# M633B.net
KiCad netlist of a schematic drawn in EAGLE
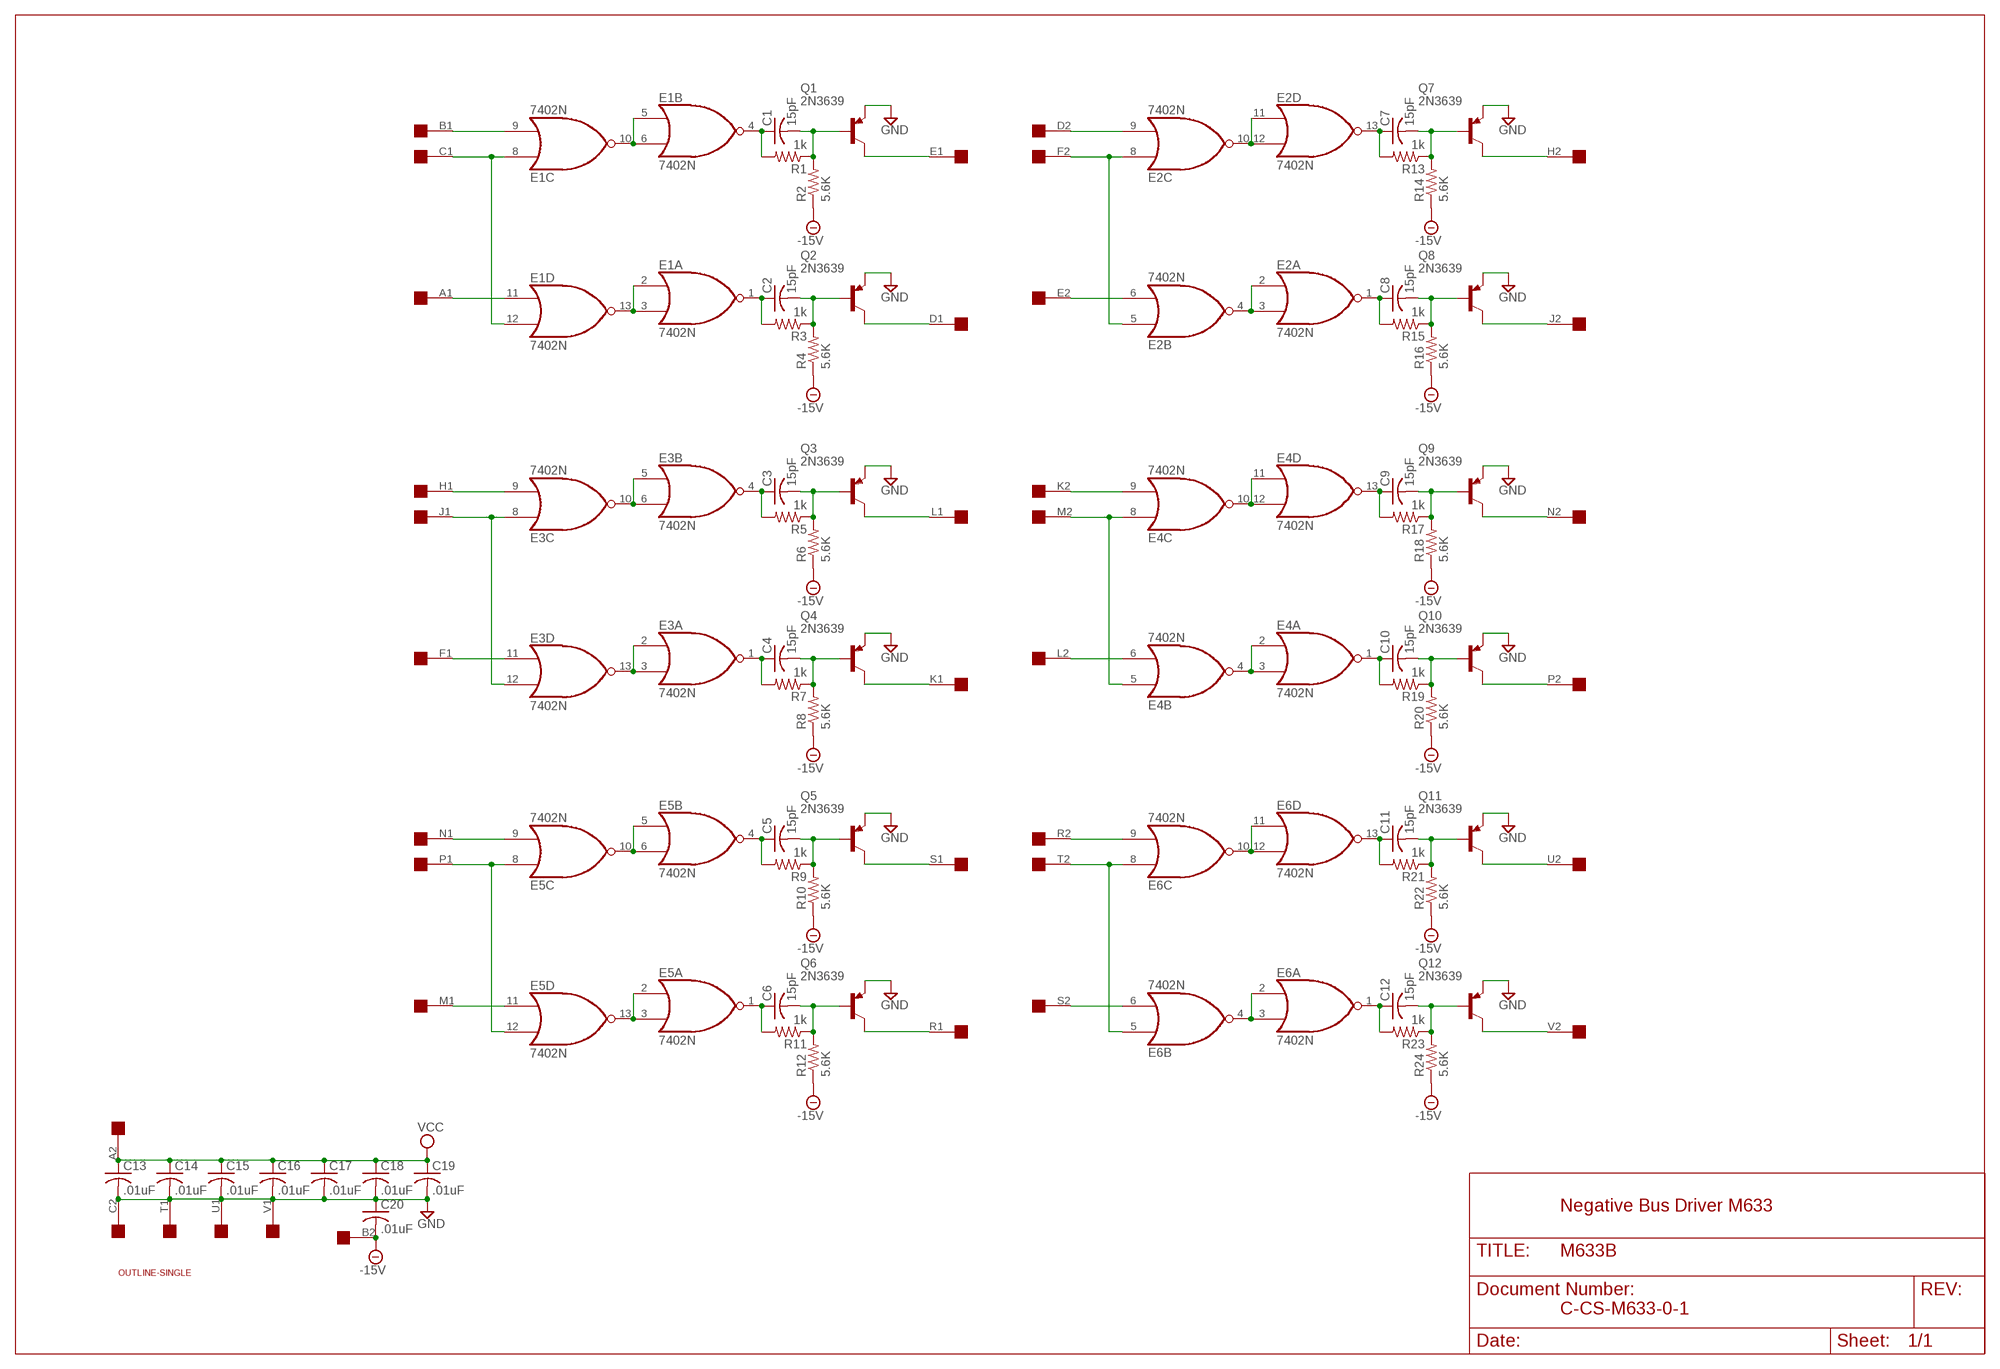
[diagram p0: schematic, sheet 1]

(export (version "E")
  (design (tool "Eeschema 10.0.6"))
  (components
    (comp (ref "C1")
      (value "15pF")
      (footprint "eagle-import:C050-025X075")
      (libsource (lib "eagle-import") (part "C-US050-025X075"))
    )
    (comp (ref "C2")
      (value "15pF")
      (footprint "eagle-import:C050-025X075")
      (libsource (lib "eagle-import") (part "C-US050-025X075"))
    )
    (comp (ref "C3")
      (value "15pF")
      (footprint "eagle-import:C050-025X075")
      (libsource (lib "eagle-import") (part "C-US050-025X075"))
    )
    (comp (ref "C4")
      (value "15pF")
      (footprint "eagle-import:C050-025X075")
      (libsource (lib "eagle-import") (part "C-US050-025X075"))
    )
    (comp (ref "C5")
      (value "15pF")
      (footprint "eagle-import:C050-025X075")
      (libsource (lib "eagle-import") (part "C-US050-025X075"))
    )
    (comp (ref "C6")
      (value "15pF")
      (footprint "eagle-import:C050-025X075")
      (libsource (lib "eagle-import") (part "C-US050-025X075"))
    )
    (comp (ref "C7")
      (value "15pF")
      (footprint "eagle-import:C050-025X075")
      (libsource (lib "eagle-import") (part "C-US050-025X075"))
    )
    (comp (ref "C8")
      (value "15pF")
      (footprint "eagle-import:C050-025X075")
      (libsource (lib "eagle-import") (part "C-US050-025X075"))
    )
    (comp (ref "C9")
      (value "15pF")
      (footprint "eagle-import:C050-025X075")
      (libsource (lib "eagle-import") (part "C-US050-025X075"))
    )
    (comp (ref "C10")
      (value "15pF")
      (footprint "eagle-import:C050-025X075")
      (libsource (lib "eagle-import") (part "C-US050-025X075"))
    )
    (comp (ref "C11")
      (value "15pF")
      (footprint "eagle-import:C050-025X075")
      (libsource (lib "eagle-import") (part "C-US050-025X075"))
    )
    (comp (ref "C12")
      (value "15pF")
      (footprint "eagle-import:C050-025X075")
      (libsource (lib "eagle-import") (part "C-US050-025X075"))
    )
    (comp (ref "C13")
      (value ".01uF")
      (footprint "eagle-import:C050-025X075")
      (libsource (lib "eagle-import") (part "C-US050-025X075"))
    )
    (comp (ref "C14")
      (value ".01uF")
      (footprint "eagle-import:C050-025X075")
      (libsource (lib "eagle-import") (part "C-US050-025X075"))
    )
    (comp (ref "C15")
      (value ".01uF")
      (footprint "eagle-import:C050-025X075")
      (libsource (lib "eagle-import") (part "C-US050-025X075"))
    )
    (comp (ref "C16")
      (value ".01uF")
      (footprint "eagle-import:C050-025X075")
      (libsource (lib "eagle-import") (part "C-US050-025X075"))
    )
    (comp (ref "C17")
      (value ".01uF")
      (footprint "eagle-import:C050-025X075")
      (libsource (lib "eagle-import") (part "C-US050-025X075"))
    )
    (comp (ref "C18")
      (value ".01uF")
      (footprint "eagle-import:C050-025X075")
      (libsource (lib "eagle-import") (part "C-US050-025X075"))
    )
    (comp (ref "C19")
      (value ".01uF")
      (footprint "eagle-import:C050-025X075")
      (libsource (lib "eagle-import") (part "C-US050-025X075"))
    )
    (comp (ref "C20")
      (value ".01uF")
      (footprint "eagle-import:C050-025X075")
      (libsource (lib "eagle-import") (part "C-US050-025X075"))
    )
    (comp (ref "E1")
      (value "7402N")
      (footprint "eagle-import:DIL14")
      (libsource (lib "eagle-import") (part "7402N"))
    )
    (comp (ref "E2")
      (value "7402N")
      (footprint "eagle-import:DIL14")
      (libsource (lib "eagle-import") (part "7402N"))
    )
    (comp (ref "E3")
      (value "7402N")
      (footprint "eagle-import:DIL14")
      (libsource (lib "eagle-import") (part "7402N"))
    )
    (comp (ref "E4")
      (value "7402N")
      (footprint "eagle-import:DIL14")
      (libsource (lib "eagle-import") (part "7402N"))
    )
    (comp (ref "E5")
      (value "7402N")
      (footprint "eagle-import:DIL14")
      (libsource (lib "eagle-import") (part "7402N"))
    )
    (comp (ref "E6")
      (value "7402N")
      (footprint "eagle-import:DIL14")
      (libsource (lib "eagle-import") (part "7402N"))
    )
    (comp (ref "Q1")
      (value "2N3639")
      (footprint "eagle-import:TO39")
      (libsource (lib "eagle-import") (part "2N5415"))
    )
    (comp (ref "Q2")
      (value "2N3639")
      (footprint "eagle-import:TO39")
      (libsource (lib "eagle-import") (part "2N5415"))
    )
    (comp (ref "Q3")
      (value "2N3639")
      (footprint "eagle-import:TO39")
      (libsource (lib "eagle-import") (part "2N5415"))
    )
    (comp (ref "Q4")
      (value "2N3639")
      (footprint "eagle-import:TO39")
      (libsource (lib "eagle-import") (part "2N5415"))
    )
    (comp (ref "Q5")
      (value "2N3639")
      (footprint "eagle-import:TO39")
      (libsource (lib "eagle-import") (part "2N5415"))
    )
    (comp (ref "Q6")
      (value "2N3639")
      (footprint "eagle-import:TO39")
      (libsource (lib "eagle-import") (part "2N5415"))
    )
    (comp (ref "Q7")
      (value "2N3639")
      (footprint "eagle-import:TO39")
      (libsource (lib "eagle-import") (part "2N5415"))
    )
    (comp (ref "Q8")
      (value "2N3639")
      (footprint "eagle-import:TO39")
      (libsource (lib "eagle-import") (part "2N5415"))
    )
    (comp (ref "Q9")
      (value "2N3639")
      (footprint "eagle-import:TO39")
      (libsource (lib "eagle-import") (part "2N5415"))
    )
    (comp (ref "Q10")
      (value "2N3639")
      (footprint "eagle-import:TO39")
      (libsource (lib "eagle-import") (part "2N5415"))
    )
    (comp (ref "Q11")
      (value "2N3639")
      (footprint "eagle-import:TO39")
      (libsource (lib "eagle-import") (part "2N5415"))
    )
    (comp (ref "Q12")
      (value "2N3639")
      (footprint "eagle-import:TO39")
      (libsource (lib "eagle-import") (part "2N5415"))
    )
    (comp (ref "R1")
      (value "1k")
      (footprint "eagle-import:0207_10")
      (libsource (lib "eagle-import") (part "R-US_0207/10"))
    )
    (comp (ref "R2")
      (value "5.6K")
      (footprint "eagle-import:0207_10")
      (libsource (lib "eagle-import") (part "R-US_0207/10"))
    )
    (comp (ref "R3")
      (value "1k")
      (footprint "eagle-import:0207_10")
      (libsource (lib "eagle-import") (part "R-US_0207/10"))
    )
    (comp (ref "R4")
      (value "5.6K")
      (footprint "eagle-import:0207_10")
      (libsource (lib "eagle-import") (part "R-US_0207/10"))
    )
    (comp (ref "R5")
      (value "1k")
      (footprint "eagle-import:0207_10")
      (libsource (lib "eagle-import") (part "R-US_0207/10"))
    )
    (comp (ref "R6")
      (value "5.6K")
      (footprint "eagle-import:0207_10")
      (libsource (lib "eagle-import") (part "R-US_0207/10"))
    )
    (comp (ref "R7")
      (value "1k")
      (footprint "eagle-import:0207_10")
      (libsource (lib "eagle-import") (part "R-US_0207/10"))
    )
    (comp (ref "R8")
      (value "5.6K")
      (footprint "eagle-import:0207_10")
      (libsource (lib "eagle-import") (part "R-US_0207/10"))
    )
    (comp (ref "R9")
      (value "1k")
      (footprint "eagle-import:0207_10")
      (libsource (lib "eagle-import") (part "R-US_0207/10"))
    )
    (comp (ref "R10")
      (value "5.6K")
      (footprint "eagle-import:0207_10")
      (libsource (lib "eagle-import") (part "R-US_0207/10"))
    )
    (comp (ref "R11")
      (value "1k")
      (footprint "eagle-import:0207_10")
      (libsource (lib "eagle-import") (part "R-US_0207/10"))
    )
    (comp (ref "R12")
      (value "5.6K")
      (footprint "eagle-import:0207_10")
      (libsource (lib "eagle-import") (part "R-US_0207/10"))
    )
    (comp (ref "R13")
      (value "1k")
      (footprint "eagle-import:0207_10")
      (libsource (lib "eagle-import") (part "R-US_0207/10"))
    )
    (comp (ref "R14")
      (value "5.6K")
      (footprint "eagle-import:0207_10")
      (libsource (lib "eagle-import") (part "R-US_0207/10"))
    )
    (comp (ref "R15")
      (value "1k")
      (footprint "eagle-import:0207_10")
      (libsource (lib "eagle-import") (part "R-US_0207/10"))
    )
    (comp (ref "R16")
      (value "5.6K")
      (footprint "eagle-import:0207_10")
      (libsource (lib "eagle-import") (part "R-US_0207/10"))
    )
    (comp (ref "R17")
      (value "1k")
      (footprint "eagle-import:0207_10")
      (libsource (lib "eagle-import") (part "R-US_0207/10"))
    )
    (comp (ref "R18")
      (value "5.6K")
      (footprint "eagle-import:0207_10")
      (libsource (lib "eagle-import") (part "R-US_0207/10"))
    )
    (comp (ref "R19")
      (value "1k")
      (footprint "eagle-import:0207_10")
      (libsource (lib "eagle-import") (part "R-US_0207/10"))
    )
    (comp (ref "R20")
      (value "5.6K")
      (footprint "eagle-import:0207_10")
      (libsource (lib "eagle-import") (part "R-US_0207/10"))
    )
    (comp (ref "R21")
      (value "1k")
      (footprint "eagle-import:0207_10")
      (libsource (lib "eagle-import") (part "R-US_0207/10"))
    )
    (comp (ref "R22")
      (value "5.6K")
      (footprint "eagle-import:0207_10")
      (libsource (lib "eagle-import") (part "R-US_0207/10"))
    )
    (comp (ref "R23")
      (value "1k")
      (footprint "eagle-import:0207_10")
      (libsource (lib "eagle-import") (part "R-US_0207/10"))
    )
    (comp (ref "R24")
      (value "5.6K")
      (footprint "eagle-import:0207_10")
      (libsource (lib "eagle-import") (part "R-US_0207/10"))
    )
    (comp (ref "U$1")
      (value "OUTLINE-SINGLE")
      (footprint "eagle-import:SINGLE")
      (libsource (lib "eagle-import") (part "OUTLINE-SINGLE"))
    )
    (comp (ref "U$4")
      (value "SINGLE")
      (footprint "eagle-import:EDGE-CON2")
      (libsource (lib "eagle-import") (part "SINGLE"))
    )
  )
  (nets
    (net (code "1") (name "-15V") (class "Default")
      (node (ref "C20") (pin "2") (pinfunction "2_2") (pintype "passive"))
      (node (ref "R10") (pin "1") (pinfunction "1_1") (pintype "passive"))
      (node (ref "R12") (pin "1") (pinfunction "1_1") (pintype "passive"))
      (node (ref "R14") (pin "1") (pinfunction "1_1") (pintype "passive"))
      (node (ref "R16") (pin "1") (pinfunction "1_1") (pintype "passive"))
      (node (ref "R18") (pin "1") (pinfunction "1_1") (pintype "passive"))
      (node (ref "R2") (pin "1") (pinfunction "1_1") (pintype "passive"))
      (node (ref "R20") (pin "1") (pinfunction "1_1") (pintype "passive"))
      (node (ref "R22") (pin "1") (pinfunction "1_1") (pintype "passive"))
      (node (ref "R24") (pin "1") (pinfunction "1_1") (pintype "passive"))
      (node (ref "R4") (pin "1") (pinfunction "1_1") (pintype "passive"))
      (node (ref "R6") (pin "1") (pinfunction "1_1") (pintype "passive"))
      (node (ref "R8") (pin "1") (pinfunction "1_1") (pintype "passive"))
      (node (ref "U$4") (pin "B2") (pinfunction "1_B2") (pintype "bidirectional"))
    )
    (net (code "2") (name "GND") (class "Default")
      (node (ref "C13") (pin "2") (pinfunction "2_2") (pintype "passive"))
      (node (ref "C14") (pin "2") (pinfunction "2_2") (pintype "passive"))
      (node (ref "C15") (pin "2") (pinfunction "2_2") (pintype "passive"))
      (node (ref "C16") (pin "2") (pinfunction "2_2") (pintype "passive"))
      (node (ref "C17") (pin "2") (pinfunction "2_2") (pintype "passive"))
      (node (ref "C18") (pin "2") (pinfunction "2_2") (pintype "passive"))
      (node (ref "C19") (pin "2") (pinfunction "2_2") (pintype "passive"))
      (node (ref "C20") (pin "1") (pinfunction "1_1") (pintype "passive"))
      (node (ref "Q1") (pin "1") (pinfunction "E_1") (pintype "passive"))
      (node (ref "Q10") (pin "1") (pinfunction "E_1") (pintype "passive"))
      (node (ref "Q11") (pin "1") (pinfunction "E_1") (pintype "passive"))
      (node (ref "Q12") (pin "1") (pinfunction "E_1") (pintype "passive"))
      (node (ref "Q2") (pin "1") (pinfunction "E_1") (pintype "passive"))
      (node (ref "Q3") (pin "1") (pinfunction "E_1") (pintype "passive"))
      (node (ref "Q4") (pin "1") (pinfunction "E_1") (pintype "passive"))
      (node (ref "Q5") (pin "1") (pinfunction "E_1") (pintype "passive"))
      (node (ref "Q6") (pin "1") (pinfunction "E_1") (pintype "passive"))
      (node (ref "Q7") (pin "1") (pinfunction "E_1") (pintype "passive"))
      (node (ref "Q8") (pin "1") (pinfunction "E_1") (pintype "passive"))
      (node (ref "Q9") (pin "1") (pinfunction "E_1") (pintype "passive"))
      (node (ref "U$4") (pin "C2") (pinfunction "1_C2") (pintype "bidirectional"))
      (node (ref "U$4") (pin "T1") (pinfunction "1_T1") (pintype "bidirectional"))
      (node (ref "U$4") (pin "U1") (pinfunction "1_U1") (pintype "bidirectional"))
      (node (ref "U$4") (pin "V1") (pinfunction "1_V1") (pintype "bidirectional"))
    )
    (net (code "3") (name "Net-(E1A-I0)") (class "Default")
      (node (ref "E1") (pin "13") (pinfunction "O_13") (pintype "output"))
      (node (ref "E1") (pin "2") (pinfunction "I0_2") (pintype "input"))
      (node (ref "E1") (pin "3") (pinfunction "I1_3") (pintype "input"))
    )
    (net (code "4") (name "Net-(E1A-O)") (class "Default")
      (node (ref "C2") (pin "1") (pinfunction "1_1") (pintype "passive"))
      (node (ref "E1") (pin "1") (pinfunction "O_1") (pintype "output"))
      (node (ref "R3") (pin "2") (pinfunction "2_2") (pintype "passive"))
    )
    (net (code "5") (name "Net-(E1B-I0)") (class "Default")
      (node (ref "E1") (pin "10") (pinfunction "O_10") (pintype "output"))
      (node (ref "E1") (pin "5") (pinfunction "I0_5") (pintype "input"))
      (node (ref "E1") (pin "6") (pinfunction "I1_6") (pintype "input"))
    )
    (net (code "6") (name "Net-(E1B-O)") (class "Default")
      (node (ref "C1") (pin "1") (pinfunction "1_1") (pintype "passive"))
      (node (ref "E1") (pin "4") (pinfunction "O_4") (pintype "output"))
      (node (ref "R1") (pin "2") (pinfunction "2_2") (pintype "passive"))
    )
    (net (code "7") (name "Net-(E1C-I0)") (class "Default")
      (node (ref "E1") (pin "12") (pinfunction "I1_12") (pintype "input"))
      (node (ref "E1") (pin "8") (pinfunction "I0_8") (pintype "input"))
      (node (ref "U$4") (pin "C1") (pinfunction "1_C1") (pintype "bidirectional"))
    )
    (net (code "8") (name "Net-(E1C-I1)") (class "Default")
      (node (ref "E1") (pin "9") (pinfunction "I1_9") (pintype "input"))
      (node (ref "U$4") (pin "B1") (pinfunction "1_B1") (pintype "bidirectional"))
    )
    (net (code "9") (name "Net-(E1D-I0)") (class "Default")
      (node (ref "E1") (pin "11") (pinfunction "I0_11") (pintype "input"))
      (node (ref "U$4") (pin "A1") (pinfunction "1_A1") (pintype "bidirectional"))
    )
    (net (code "10") (name "Net-(E2A-I0)") (class "Default")
      (node (ref "E2") (pin "2") (pinfunction "I0_2") (pintype "input"))
      (node (ref "E2") (pin "3") (pinfunction "I1_3") (pintype "input"))
      (node (ref "E2") (pin "4") (pinfunction "O_4") (pintype "output"))
    )
    (net (code "11") (name "Net-(E2A-O)") (class "Default")
      (node (ref "C8") (pin "1") (pinfunction "1_1") (pintype "passive"))
      (node (ref "E2") (pin "1") (pinfunction "O_1") (pintype "output"))
      (node (ref "R15") (pin "2") (pinfunction "2_2") (pintype "passive"))
    )
    (net (code "12") (name "Net-(E2B-I0)") (class "Default")
      (node (ref "E2") (pin "5") (pinfunction "I0_5") (pintype "input"))
      (node (ref "E2") (pin "8") (pinfunction "I0_8") (pintype "input"))
      (node (ref "U$4") (pin "F2") (pinfunction "1_F2") (pintype "bidirectional"))
    )
    (net (code "13") (name "Net-(E2B-I1)") (class "Default")
      (node (ref "E2") (pin "6") (pinfunction "I1_6") (pintype "input"))
      (node (ref "U$4") (pin "E2") (pinfunction "1_E2") (pintype "bidirectional"))
    )
    (net (code "14") (name "Net-(E2C-I1)") (class "Default")
      (node (ref "E2") (pin "9") (pinfunction "I1_9") (pintype "input"))
      (node (ref "U$4") (pin "D2") (pinfunction "1_D2") (pintype "bidirectional"))
    )
    (net (code "15") (name "Net-(E2C-O)") (class "Default")
      (node (ref "E2") (pin "10") (pinfunction "O_10") (pintype "output"))
      (node (ref "E2") (pin "11") (pinfunction "I0_11") (pintype "input"))
      (node (ref "E2") (pin "12") (pinfunction "I1_12") (pintype "input"))
    )
    (net (code "16") (name "Net-(E2D-O)") (class "Default")
      (node (ref "C7") (pin "1") (pinfunction "1_1") (pintype "passive"))
      (node (ref "E2") (pin "13") (pinfunction "O_13") (pintype "output"))
      (node (ref "R13") (pin "2") (pinfunction "2_2") (pintype "passive"))
    )
    (net (code "17") (name "Net-(E3A-I0)") (class "Default")
      (node (ref "E3") (pin "13") (pinfunction "O_13") (pintype "output"))
      (node (ref "E3") (pin "2") (pinfunction "I0_2") (pintype "input"))
      (node (ref "E3") (pin "3") (pinfunction "I1_3") (pintype "input"))
    )
    (net (code "18") (name "Net-(E3A-O)") (class "Default")
      (node (ref "C4") (pin "1") (pinfunction "1_1") (pintype "passive"))
      (node (ref "E3") (pin "1") (pinfunction "O_1") (pintype "output"))
      (node (ref "R7") (pin "2") (pinfunction "2_2") (pintype "passive"))
    )
    (net (code "19") (name "Net-(E3B-I0)") (class "Default")
      (node (ref "E3") (pin "10") (pinfunction "O_10") (pintype "output"))
      (node (ref "E3") (pin "5") (pinfunction "I0_5") (pintype "input"))
      (node (ref "E3") (pin "6") (pinfunction "I1_6") (pintype "input"))
    )
    (net (code "20") (name "Net-(E3B-O)") (class "Default")
      (node (ref "C3") (pin "1") (pinfunction "1_1") (pintype "passive"))
      (node (ref "E3") (pin "4") (pinfunction "O_4") (pintype "output"))
      (node (ref "R5") (pin "2") (pinfunction "2_2") (pintype "passive"))
    )
    (net (code "21") (name "Net-(E3C-I0)") (class "Default")
      (node (ref "E3") (pin "12") (pinfunction "I1_12") (pintype "input"))
      (node (ref "E3") (pin "8") (pinfunction "I0_8") (pintype "input"))
      (node (ref "U$4") (pin "J1") (pinfunction "1_J1") (pintype "bidirectional"))
    )
    (net (code "22") (name "Net-(E3C-I1)") (class "Default")
      (node (ref "E3") (pin "9") (pinfunction "I1_9") (pintype "input"))
      (node (ref "U$4") (pin "H1") (pinfunction "1_H1") (pintype "bidirectional"))
    )
    (net (code "23") (name "Net-(E3D-I0)") (class "Default")
      (node (ref "E3") (pin "11") (pinfunction "I0_11") (pintype "input"))
      (node (ref "U$4") (pin "F1") (pinfunction "1_F1") (pintype "bidirectional"))
    )
    (net (code "24") (name "Net-(E4A-I0)") (class "Default")
      (node (ref "E4") (pin "2") (pinfunction "I0_2") (pintype "input"))
      (node (ref "E4") (pin "3") (pinfunction "I1_3") (pintype "input"))
      (node (ref "E4") (pin "4") (pinfunction "O_4") (pintype "output"))
    )
    (net (code "25") (name "Net-(E4A-O)") (class "Default")
      (node (ref "C10") (pin "1") (pinfunction "1_1") (pintype "passive"))
      (node (ref "E4") (pin "1") (pinfunction "O_1") (pintype "output"))
      (node (ref "R19") (pin "2") (pinfunction "2_2") (pintype "passive"))
    )
    (net (code "26") (name "Net-(E4B-I0)") (class "Default")
      (node (ref "E4") (pin "5") (pinfunction "I0_5") (pintype "input"))
      (node (ref "E4") (pin "8") (pinfunction "I0_8") (pintype "input"))
      (node (ref "U$4") (pin "M2") (pinfunction "1_M2") (pintype "bidirectional"))
    )
    (net (code "27") (name "Net-(E4B-I1)") (class "Default")
      (node (ref "E4") (pin "6") (pinfunction "I1_6") (pintype "input"))
      (node (ref "U$4") (pin "L2") (pinfunction "1_L2") (pintype "bidirectional"))
    )
    (net (code "28") (name "Net-(E4C-I1)") (class "Default")
      (node (ref "E4") (pin "9") (pinfunction "I1_9") (pintype "input"))
      (node (ref "U$4") (pin "K2") (pinfunction "1_K2") (pintype "bidirectional"))
    )
    (net (code "29") (name "Net-(E4C-O)") (class "Default")
      (node (ref "E4") (pin "10") (pinfunction "O_10") (pintype "output"))
      (node (ref "E4") (pin "11") (pinfunction "I0_11") (pintype "input"))
      (node (ref "E4") (pin "12") (pinfunction "I1_12") (pintype "input"))
    )
    (net (code "30") (name "Net-(E4D-O)") (class "Default")
      (node (ref "C9") (pin "1") (pinfunction "1_1") (pintype "passive"))
      (node (ref "E4") (pin "13") (pinfunction "O_13") (pintype "output"))
      (node (ref "R17") (pin "2") (pinfunction "2_2") (pintype "passive"))
    )
    (net (code "31") (name "Net-(E5A-I0)") (class "Default")
      (node (ref "E5") (pin "13") (pinfunction "O_13") (pintype "output"))
      (node (ref "E5") (pin "2") (pinfunction "I0_2") (pintype "input"))
      (node (ref "E5") (pin "3") (pinfunction "I1_3") (pintype "input"))
    )
    (net (code "32") (name "Net-(E5A-O)") (class "Default")
      (node (ref "C6") (pin "1") (pinfunction "1_1") (pintype "passive"))
      (node (ref "E5") (pin "1") (pinfunction "O_1") (pintype "output"))
      (node (ref "R11") (pin "2") (pinfunction "2_2") (pintype "passive"))
    )
    (net (code "33") (name "Net-(E5B-I0)") (class "Default")
      (node (ref "E5") (pin "10") (pinfunction "O_10") (pintype "output"))
      (node (ref "E5") (pin "5") (pinfunction "I0_5") (pintype "input"))
      (node (ref "E5") (pin "6") (pinfunction "I1_6") (pintype "input"))
    )
    (net (code "34") (name "Net-(E5B-O)") (class "Default")
      (node (ref "C5") (pin "1") (pinfunction "1_1") (pintype "passive"))
      (node (ref "E5") (pin "4") (pinfunction "O_4") (pintype "output"))
      (node (ref "R9") (pin "2") (pinfunction "2_2") (pintype "passive"))
    )
    (net (code "35") (name "Net-(E5C-I0)") (class "Default")
      (node (ref "E5") (pin "12") (pinfunction "I1_12") (pintype "input"))
      (node (ref "E5") (pin "8") (pinfunction "I0_8") (pintype "input"))
      (node (ref "U$4") (pin "P1") (pinfunction "1_P1") (pintype "bidirectional"))
    )
    (net (code "36") (name "Net-(E5C-I1)") (class "Default")
      (node (ref "E5") (pin "9") (pinfunction "I1_9") (pintype "input"))
      (node (ref "U$4") (pin "N1") (pinfunction "1_N1") (pintype "bidirectional"))
    )
    (net (code "37") (name "Net-(E5D-I0)") (class "Default")
      (node (ref "E5") (pin "11") (pinfunction "I0_11") (pintype "input"))
      (node (ref "U$4") (pin "M1") (pinfunction "1_M1") (pintype "bidirectional"))
    )
    (net (code "38") (name "Net-(E6A-I0)") (class "Default")
      (node (ref "E6") (pin "2") (pinfunction "I0_2") (pintype "input"))
      (node (ref "E6") (pin "3") (pinfunction "I1_3") (pintype "input"))
      (node (ref "E6") (pin "4") (pinfunction "O_4") (pintype "output"))
    )
    (net (code "39") (name "Net-(E6A-O)") (class "Default")
      (node (ref "C12") (pin "1") (pinfunction "1_1") (pintype "passive"))
      (node (ref "E6") (pin "1") (pinfunction "O_1") (pintype "output"))
      (node (ref "R23") (pin "2") (pinfunction "2_2") (pintype "passive"))
    )
    (net (code "40") (name "Net-(E6B-I0)") (class "Default")
      (node (ref "E6") (pin "5") (pinfunction "I0_5") (pintype "input"))
      (node (ref "E6") (pin "8") (pinfunction "I0_8") (pintype "input"))
      (node (ref "U$4") (pin "T2") (pinfunction "1_T2") (pintype "bidirectional"))
    )
    (net (code "41") (name "Net-(E6B-I1)") (class "Default")
      (node (ref "E6") (pin "6") (pinfunction "I1_6") (pintype "input"))
      (node (ref "U$4") (pin "S2") (pinfunction "1_S2") (pintype "bidirectional"))
    )
    (net (code "42") (name "Net-(E6C-I1)") (class "Default")
      (node (ref "E6") (pin "9") (pinfunction "I1_9") (pintype "input"))
      (node (ref "U$4") (pin "R2") (pinfunction "1_R2") (pintype "bidirectional"))
    )
    (net (code "43") (name "Net-(E6C-O)") (class "Default")
      (node (ref "E6") (pin "10") (pinfunction "O_10") (pintype "output"))
      (node (ref "E6") (pin "11") (pinfunction "I0_11") (pintype "input"))
      (node (ref "E6") (pin "12") (pinfunction "I1_12") (pintype "input"))
    )
    (net (code "44") (name "Net-(E6D-O)") (class "Default")
      (node (ref "C11") (pin "1") (pinfunction "1_1") (pintype "passive"))
      (node (ref "E6") (pin "13") (pinfunction "O_13") (pintype "output"))
      (node (ref "R21") (pin "2") (pinfunction "2_2") (pintype "passive"))
    )
    (net (code "45") (name "Net-(Q1-B)") (class "Default")
      (node (ref "C1") (pin "2") (pinfunction "2_2") (pintype "passive"))
      (node (ref "Q1") (pin "2") (pinfunction "B_2") (pintype "passive"))
      (node (ref "R1") (pin "1") (pinfunction "1_1") (pintype "passive"))
      (node (ref "R2") (pin "2") (pinfunction "2_2") (pintype "passive"))
    )
    (net (code "46") (name "Net-(Q1-C)") (class "Default")
      (node (ref "Q1") (pin "3") (pinfunction "C_3") (pintype "passive"))
      (node (ref "U$4") (pin "E1") (pinfunction "1_E1") (pintype "bidirectional"))
    )
    (net (code "47") (name "Net-(Q2-B)") (class "Default")
      (node (ref "C2") (pin "2") (pinfunction "2_2") (pintype "passive"))
      (node (ref "Q2") (pin "2") (pinfunction "B_2") (pintype "passive"))
      (node (ref "R3") (pin "1") (pinfunction "1_1") (pintype "passive"))
      (node (ref "R4") (pin "2") (pinfunction "2_2") (pintype "passive"))
    )
    (net (code "48") (name "Net-(Q2-C)") (class "Default")
      (node (ref "Q2") (pin "3") (pinfunction "C_3") (pintype "passive"))
      (node (ref "U$4") (pin "D1") (pinfunction "1_D1") (pintype "bidirectional"))
    )
    (net (code "49") (name "Net-(Q3-B)") (class "Default")
      (node (ref "C3") (pin "2") (pinfunction "2_2") (pintype "passive"))
      (node (ref "Q3") (pin "2") (pinfunction "B_2") (pintype "passive"))
      (node (ref "R5") (pin "1") (pinfunction "1_1") (pintype "passive"))
      (node (ref "R6") (pin "2") (pinfunction "2_2") (pintype "passive"))
    )
    (net (code "50") (name "Net-(Q3-C)") (class "Default")
      (node (ref "Q3") (pin "3") (pinfunction "C_3") (pintype "passive"))
      (node (ref "U$4") (pin "L1") (pinfunction "1_L1") (pintype "bidirectional"))
    )
    (net (code "51") (name "Net-(Q4-B)") (class "Default")
      (node (ref "C4") (pin "2") (pinfunction "2_2") (pintype "passive"))
      (node (ref "Q4") (pin "2") (pinfunction "B_2") (pintype "passive"))
      (node (ref "R7") (pin "1") (pinfunction "1_1") (pintype "passive"))
      (node (ref "R8") (pin "2") (pinfunction "2_2") (pintype "passive"))
    )
    (net (code "52") (name "Net-(Q4-C)") (class "Default")
      (node (ref "Q4") (pin "3") (pinfunction "C_3") (pintype "passive"))
      (node (ref "U$4") (pin "K1") (pinfunction "1_K1") (pintype "bidirectional"))
    )
    (net (code "53") (name "Net-(Q5-B)") (class "Default")
      (node (ref "C5") (pin "2") (pinfunction "2_2") (pintype "passive"))
      (node (ref "Q5") (pin "2") (pinfunction "B_2") (pintype "passive"))
      (node (ref "R10") (pin "2") (pinfunction "2_2") (pintype "passive"))
      (node (ref "R9") (pin "1") (pinfunction "1_1") (pintype "passive"))
    )
    (net (code "54") (name "Net-(Q5-C)") (class "Default")
      (node (ref "Q5") (pin "3") (pinfunction "C_3") (pintype "passive"))
      (node (ref "U$4") (pin "S1") (pinfunction "1_S1") (pintype "bidirectional"))
    )
    (net (code "55") (name "Net-(Q6-B)") (class "Default")
      (node (ref "C6") (pin "2") (pinfunction "2_2") (pintype "passive"))
      (node (ref "Q6") (pin "2") (pinfunction "B_2") (pintype "passive"))
      (node (ref "R11") (pin "1") (pinfunction "1_1") (pintype "passive"))
      (node (ref "R12") (pin "2") (pinfunction "2_2") (pintype "passive"))
    )
    (net (code "56") (name "Net-(Q6-C)") (class "Default")
      (node (ref "Q6") (pin "3") (pinfunction "C_3") (pintype "passive"))
      (node (ref "U$4") (pin "R1") (pinfunction "1_R1") (pintype "bidirectional"))
    )
    (net (code "57") (name "Net-(Q7-B)") (class "Default")
      (node (ref "C7") (pin "2") (pinfunction "2_2") (pintype "passive"))
      (node (ref "Q7") (pin "2") (pinfunction "B_2") (pintype "passive"))
      (node (ref "R13") (pin "1") (pinfunction "1_1") (pintype "passive"))
      (node (ref "R14") (pin "2") (pinfunction "2_2") (pintype "passive"))
    )
    (net (code "58") (name "Net-(Q7-C)") (class "Default")
      (node (ref "Q7") (pin "3") (pinfunction "C_3") (pintype "passive"))
      (node (ref "U$4") (pin "H2") (pinfunction "1_H2") (pintype "bidirectional"))
    )
    (net (code "59") (name "Net-(Q8-B)") (class "Default")
      (node (ref "C8") (pin "2") (pinfunction "2_2") (pintype "passive"))
      (node (ref "Q8") (pin "2") (pinfunction "B_2") (pintype "passive"))
      (node (ref "R15") (pin "1") (pinfunction "1_1") (pintype "passive"))
      (node (ref "R16") (pin "2") (pinfunction "2_2") (pintype "passive"))
    )
    (net (code "60") (name "Net-(Q8-C)") (class "Default")
      (node (ref "Q8") (pin "3") (pinfunction "C_3") (pintype "passive"))
      (node (ref "U$4") (pin "J2") (pinfunction "1_J2") (pintype "bidirectional"))
    )
    (net (code "61") (name "Net-(Q9-B)") (class "Default")
      (node (ref "C9") (pin "2") (pinfunction "2_2") (pintype "passive"))
      (node (ref "Q9") (pin "2") (pinfunction "B_2") (pintype "passive"))
      (node (ref "R17") (pin "1") (pinfunction "1_1") (pintype "passive"))
      (node (ref "R18") (pin "2") (pinfunction "2_2") (pintype "passive"))
    )
    (net (code "62") (name "Net-(Q9-C)") (class "Default")
      (node (ref "Q9") (pin "3") (pinfunction "C_3") (pintype "passive"))
      (node (ref "U$4") (pin "N2") (pinfunction "1_N2") (pintype "bidirectional"))
    )
    (net (code "63") (name "Net-(Q10-B)") (class "Default")
      (node (ref "C10") (pin "2") (pinfunction "2_2") (pintype "passive"))
      (node (ref "Q10") (pin "2") (pinfunction "B_2") (pintype "passive"))
      (node (ref "R19") (pin "1") (pinfunction "1_1") (pintype "passive"))
      (node (ref "R20") (pin "2") (pinfunction "2_2") (pintype "passive"))
    )
    (net (code "64") (name "Net-(Q10-C)") (class "Default")
      (node (ref "Q10") (pin "3") (pinfunction "C_3") (pintype "passive"))
      (node (ref "U$4") (pin "P2") (pinfunction "1_P2") (pintype "bidirectional"))
    )
    (net (code "65") (name "Net-(Q11-B)") (class "Default")
      (node (ref "C11") (pin "2") (pinfunction "2_2") (pintype "passive"))
      (node (ref "Q11") (pin "2") (pinfunction "B_2") (pintype "passive"))
      (node (ref "R21") (pin "1") (pinfunction "1_1") (pintype "passive"))
      (node (ref "R22") (pin "2") (pinfunction "2_2") (pintype "passive"))
    )
    (net (code "66") (name "Net-(Q11-C)") (class "Default")
      (node (ref "Q11") (pin "3") (pinfunction "C_3") (pintype "passive"))
      (node (ref "U$4") (pin "U2") (pinfunction "1_U2") (pintype "bidirectional"))
    )
    (net (code "67") (name "Net-(Q12-B)") (class "Default")
      (node (ref "C12") (pin "2") (pinfunction "2_2") (pintype "passive"))
      (node (ref "Q12") (pin "2") (pinfunction "B_2") (pintype "passive"))
      (node (ref "R23") (pin "1") (pinfunction "1_1") (pintype "passive"))
      (node (ref "R24") (pin "2") (pinfunction "2_2") (pintype "passive"))
    )
    (net (code "68") (name "Net-(Q12-C)") (class "Default")
      (node (ref "Q12") (pin "3") (pinfunction "C_3") (pintype "passive"))
      (node (ref "U$4") (pin "V2") (pinfunction "1_V2") (pintype "bidirectional"))
    )
    (net (code "69") (name "VCC") (class "Default")
      (node (ref "C13") (pin "1") (pinfunction "1_1") (pintype "passive"))
      (node (ref "C14") (pin "1") (pinfunction "1_1") (pintype "passive"))
      (node (ref "C15") (pin "1") (pinfunction "1_1") (pintype "passive"))
      (node (ref "C16") (pin "1") (pinfunction "1_1") (pintype "passive"))
      (node (ref "C17") (pin "1") (pinfunction "1_1") (pintype "passive"))
      (node (ref "C18") (pin "1") (pinfunction "1_1") (pintype "passive"))
      (node (ref "C19") (pin "1") (pinfunction "1_1") (pintype "passive"))
      (node (ref "U$4") (pin "A2") (pinfunction "1_A2") (pintype "bidirectional"))
    )
  )
)
